# V1.net
KiCad netlist of a schematic drawn in EAGLE
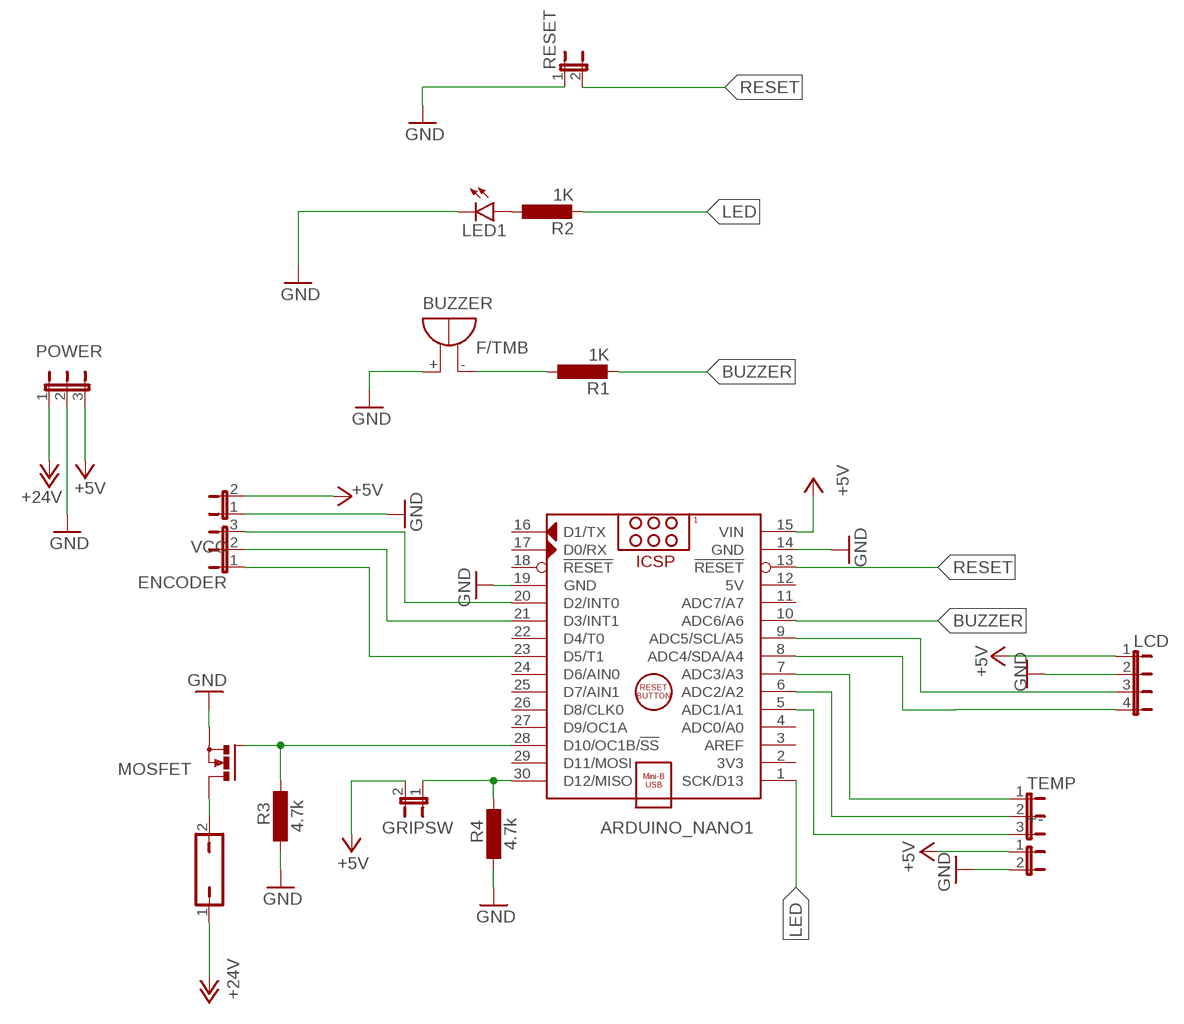
[diagram p0: schematic, sheet 1]

(export (version "E")
  (design (tool "Eeschema 10.0.6"))
  (components
    (comp (ref "+-")
      (value "JP1E")
      (footprint "eagle-import:JP1")
      (libsource (lib "eagle-import") (part "JP1E"))
    )
    (comp (ref "ARDUINO_NANO1")
      (value "ARDUINO_NANO")
      (footprint "eagle-import:ARDUINO_NANO")
      (libsource (lib "eagle-import") (part "ARDUINO_NANO"))
    )
    (comp (ref "BUZZER")
      (value "F/TMB")
      (footprint "eagle-import:F_TMB")
      (libsource (lib "eagle-import") (part "F/TMB"))
    )
    (comp (ref "ENCODER")
      (value "JP2E")
      (footprint "eagle-import:JP2")
      (libsource (lib "eagle-import") (part "JP2E"))
    )
    (comp (ref "GRIPSW")
      (value "JP1E")
      (footprint "eagle-import:JP1")
      (libsource (lib "eagle-import") (part "JP1E"))
    )
    (comp (ref "HEATER")
      (value "794681-2")
      (footprint "eagle-import:JP1")
      (libsource (lib "eagle-import") (part "JP1Q"))
    )
    (comp (ref "LCD")
      (value "JP4E")
      (footprint "eagle-import:JP4")
      (libsource (lib "eagle-import") (part "JP4E"))
    )
    (comp (ref "LED1")
      (value "LED3MM")
      (footprint "eagle-import:LED3MM")
      (libsource (lib "eagle-import") (part "LED3MM"))
    )
    (comp (ref "MOSFET")
      (value "IRLB8721")
      (footprint "eagle-import:TO220BV")
      (libsource (lib "eagle-import") (part "PMOSFET_NTO220BV"))
    )
    (comp (ref "POWER")
      (value "JP2E")
      (footprint "eagle-import:JP2")
      (libsource (lib "eagle-import") (part "JP2E"))
    )
    (comp (ref "R1")
      (value "1K")
      (footprint "eagle-import:0204_7")
      (libsource (lib "eagle-import") (part "L-EU0204/7"))
    )
    (comp (ref "R2")
      (value "1K")
      (footprint "eagle-import:0204_7")
      (libsource (lib "eagle-import") (part "L-EU0204/7"))
    )
    (comp (ref "R3")
      (value "4.7k")
      (footprint "eagle-import:0204_7")
      (libsource (lib "eagle-import") (part "L-EU0204/7"))
    )
    (comp (ref "R4")
      (value "4.7k")
      (footprint "eagle-import:0204_7")
      (libsource (lib "eagle-import") (part "L-EU0204/7"))
    )
    (comp (ref "RESET")
      (value "JP1E")
      (footprint "eagle-import:JP1")
      (libsource (lib "eagle-import") (part "JP1E"))
    )
    (comp (ref "TEMP")
      (value "JP2E")
      (footprint "eagle-import:JP2")
      (libsource (lib "eagle-import") (part "JP2E"))
    )
    (comp (ref "VCC")
      (value "JP1E")
      (footprint "eagle-import:JP1")
      (libsource (lib "eagle-import") (part "JP1E"))
    )
  )
  (nets
    (net (code "1") (name "+5V") (class "Default")
      (node (ref "+-") (pin "1") (pinfunction "1_1") (pintype "passive"))
      (node (ref "ARDUINO_NANO1") (pin "15") (pinfunction "VIN_15") (pintype "power_in"))
      (node (ref "GRIPSW") (pin "2") (pinfunction "2_2") (pintype "passive"))
      (node (ref "LCD") (pin "1") (pinfunction "1_1") (pintype "passive"))
      (node (ref "POWER") (pin "3") (pinfunction "3_3") (pintype "passive"))
      (node (ref "VCC") (pin "2") (pinfunction "2_2") (pintype "passive"))
    )
    (net (code "2") (name "+24V") (class "Default")
      (node (ref "HEATER") (pin "1") (pinfunction "1_1") (pintype "passive"))
      (node (ref "POWER") (pin "1") (pinfunction "1_1") (pintype "passive"))
    )
    (net (code "3") (name "/5V") (class "Default")
      (node (ref "ARDUINO_NANO1") (pin "12") (pinfunction "5V_12") (pintype "power_in"))
    )
    (net (code "4") (name "BUZZER") (class "Default")
      (node (ref "ARDUINO_NANO1") (pin "10") (pinfunction "ADC6/A6_10") (pintype "bidirectional"))
      (node (ref "R1") (pin "2") (pinfunction "2_2") (pintype "passive"))
    )
    (net (code "5") (name "GND") (class "Default")
      (node (ref "+-") (pin "2") (pinfunction "2_2") (pintype "passive"))
      (node (ref "ARDUINO_NANO1") (pin "14") (pinfunction "GND_14") (pintype "power_in"))
      (node (ref "ARDUINO_NANO1") (pin "19") (pinfunction "GND_19") (pintype "power_in"))
      (node (ref "BUZZER") (pin "+") (pinfunction "+_+") (pintype "passive"))
      (node (ref "LCD") (pin "2") (pinfunction "2_2") (pintype "passive"))
      (node (ref "LED1") (pin "K") (pinfunction "C_K") (pintype "passive"))
      (node (ref "MOSFET") (pin "S") (pinfunction "S_S") (pintype "passive"))
      (node (ref "POWER") (pin "2") (pinfunction "2_2") (pintype "passive"))
      (node (ref "R3") (pin "2") (pinfunction "2_2") (pintype "passive"))
      (node (ref "R4") (pin "2") (pinfunction "2_2") (pintype "passive"))
      (node (ref "RESET") (pin "1") (pinfunction "1_1") (pintype "passive"))
      (node (ref "VCC") (pin "1") (pinfunction "1_1") (pintype "passive"))
    )
    (net (code "6") (name "LED") (class "Default")
      (node (ref "ARDUINO_NANO1") (pin "1") (pinfunction "SCK/D13_1") (pintype "bidirectional"))
      (node (ref "R2") (pin "2") (pinfunction "2_2") (pintype "passive"))
    )
    (net (code "7") (name "Net-(ARDUINO_NANO1-ADC1{slash}A1)") (class "Default")
      (node (ref "ARDUINO_NANO1") (pin "5") (pinfunction "ADC1/A1_5") (pintype "bidirectional"))
      (node (ref "TEMP") (pin "3") (pinfunction "3_3") (pintype "passive"))
    )
    (net (code "8") (name "Net-(ARDUINO_NANO1-ADC2{slash}A2)") (class "Default")
      (node (ref "ARDUINO_NANO1") (pin "6") (pinfunction "ADC2/A2_6") (pintype "bidirectional"))
      (node (ref "TEMP") (pin "2") (pinfunction "2_2") (pintype "passive"))
    )
    (net (code "9") (name "Net-(ARDUINO_NANO1-ADC3{slash}A3)") (class "Default")
      (node (ref "ARDUINO_NANO1") (pin "7") (pinfunction "ADC3/A3_7") (pintype "bidirectional"))
      (node (ref "TEMP") (pin "1") (pinfunction "1_1") (pintype "passive"))
    )
    (net (code "10") (name "Net-(ARDUINO_NANO1-ADC4{slash}SDA{slash}A4)") (class "Default")
      (node (ref "ARDUINO_NANO1") (pin "8") (pinfunction "ADC4/SDA/A4_8") (pintype "bidirectional"))
      (node (ref "LCD") (pin "4") (pinfunction "4_4") (pintype "passive"))
    )
    (net (code "11") (name "Net-(ARDUINO_NANO1-ADC5{slash}SCL{slash}A5)") (class "Default")
      (node (ref "ARDUINO_NANO1") (pin "9") (pinfunction "ADC5/SCL/A5_9") (pintype "bidirectional"))
      (node (ref "LCD") (pin "3") (pinfunction "3_3") (pintype "passive"))
    )
    (net (code "12") (name "Net-(ARDUINO_NANO1-D2{slash}INT0)") (class "Default")
      (node (ref "ARDUINO_NANO1") (pin "20") (pinfunction "D2/INT0_20") (pintype "bidirectional"))
      (node (ref "ENCODER") (pin "3") (pinfunction "3_3") (pintype "passive"))
    )
    (net (code "13") (name "Net-(ARDUINO_NANO1-D3{slash}INT1)") (class "Default")
      (node (ref "ARDUINO_NANO1") (pin "21") (pinfunction "D3/INT1_21") (pintype "bidirectional"))
      (node (ref "ENCODER") (pin "2") (pinfunction "2_2") (pintype "passive"))
    )
    (net (code "14") (name "Net-(ARDUINO_NANO1-D5{slash}T1)") (class "Default")
      (node (ref "ARDUINO_NANO1") (pin "23") (pinfunction "D5/T1_23") (pintype "bidirectional"))
      (node (ref "ENCODER") (pin "1") (pinfunction "1_1") (pintype "passive"))
    )
    (net (code "15") (name "Net-(ARDUINO_NANO1-D10{slash}OC1B{slash}~{SS})") (class "Default")
      (node (ref "ARDUINO_NANO1") (pin "28") (pinfunction "D10/OC1B/~{SS}_28") (pintype "bidirectional"))
      (node (ref "MOSFET") (pin "G") (pinfunction "G_G") (pintype "passive"))
      (node (ref "R3") (pin "1") (pinfunction "1_1") (pintype "passive"))
    )
    (net (code "16") (name "Net-(ARDUINO_NANO1-D12{slash}MISO)") (class "Default")
      (node (ref "ARDUINO_NANO1") (pin "30") (pinfunction "D12/MISO_30") (pintype "bidirectional"))
      (node (ref "GRIPSW") (pin "1") (pinfunction "1_1") (pintype "passive"))
      (node (ref "R4") (pin "1") (pinfunction "1_1") (pintype "passive"))
    )
    (net (code "17") (name "Net-(BUZZER-Pad-)") (class "Default")
      (node (ref "BUZZER") (pin "-") (pinfunction "-_-") (pintype "passive"))
      (node (ref "R1") (pin "1") (pinfunction "1_1") (pintype "passive"))
    )
    (net (code "18") (name "Net-(HEATER-Pad2)") (class "Default")
      (node (ref "HEATER") (pin "2") (pinfunction "2_2") (pintype "passive"))
      (node (ref "MOSFET") (pin "D") (pinfunction "D_D") (pintype "passive"))
    )
    (net (code "19") (name "Net-(LED1-PadA)") (class "Default")
      (node (ref "LED1") (pin "A") (pinfunction "A_A") (pintype "passive"))
      (node (ref "R2") (pin "1") (pinfunction "1_1") (pintype "passive"))
    )
    (net (code "20") (name "RESET") (class "Default")
      (node (ref "ARDUINO_NANO1") (pin "13") (pinfunction "~{RESET}_13") (pintype "input"))
      (node (ref "RESET") (pin "2") (pinfunction "2_2") (pintype "passive"))
    )
    (net (code "21") (name "unconnected-(ARDUINO_NANO1-3V3-Pad2)") (class "Default")
      (node (ref "ARDUINO_NANO1") (pin "2") (pinfunction "3V3_2") (pintype "output"))
    )
    (net (code "22") (name "unconnected-(ARDUINO_NANO1-ADC0{slash}A0-Pad4)") (class "Default")
      (node (ref "ARDUINO_NANO1") (pin "4") (pinfunction "ADC0/A0_4") (pintype "bidirectional"))
    )
    (net (code "23") (name "unconnected-(ARDUINO_NANO1-ADC7{slash}A7-Pad11)") (class "Default")
      (node (ref "ARDUINO_NANO1") (pin "11") (pinfunction "ADC7/A7_11") (pintype "bidirectional"))
    )
    (net (code "24") (name "unconnected-(ARDUINO_NANO1-AREF-Pad3)") (class "Default")
      (node (ref "ARDUINO_NANO1") (pin "3") (pinfunction "AREF_3") (pintype "input"))
    )
    (net (code "25") (name "unconnected-(ARDUINO_NANO1-D0{slash}RX-Pad17)") (class "Default")
      (node (ref "ARDUINO_NANO1") (pin "17") (pinfunction "D0/RX_17") (pintype "bidirectional"))
    )
    (net (code "26") (name "unconnected-(ARDUINO_NANO1-D1{slash}TX-Pad16)") (class "Default")
      (node (ref "ARDUINO_NANO1") (pin "16") (pinfunction "D1/TX_16") (pintype "bidirectional"))
    )
    (net (code "27") (name "unconnected-(ARDUINO_NANO1-D4{slash}T0-Pad22)") (class "Default")
      (node (ref "ARDUINO_NANO1") (pin "22") (pinfunction "D4/T0_22") (pintype "bidirectional"))
    )
    (net (code "28") (name "unconnected-(ARDUINO_NANO1-D6{slash}AIN0-Pad24)") (class "Default")
      (node (ref "ARDUINO_NANO1") (pin "24") (pinfunction "D6/AIN0_24") (pintype "bidirectional"))
    )
    (net (code "29") (name "unconnected-(ARDUINO_NANO1-D7{slash}AIN1-Pad25)") (class "Default")
      (node (ref "ARDUINO_NANO1") (pin "25") (pinfunction "D7/AIN1_25") (pintype "bidirectional"))
    )
    (net (code "30") (name "unconnected-(ARDUINO_NANO1-D8{slash}CLK0-Pad26)") (class "Default")
      (node (ref "ARDUINO_NANO1") (pin "26") (pinfunction "D8/CLK0_26") (pintype "bidirectional"))
    )
    (net (code "31") (name "unconnected-(ARDUINO_NANO1-D9{slash}OC1A-Pad27)") (class "Default")
      (node (ref "ARDUINO_NANO1") (pin "27") (pinfunction "D9/OC1A_27") (pintype "bidirectional"))
    )
    (net (code "32") (name "unconnected-(ARDUINO_NANO1-D11{slash}MOSI-Pad29)") (class "Default")
      (node (ref "ARDUINO_NANO1") (pin "29") (pinfunction "D11/MOSI_29") (pintype "bidirectional"))
    )
    (net (code "33") (name "unconnected-(ARDUINO_NANO1-~{RESET}-Pad18)") (class "Default")
      (node (ref "ARDUINO_NANO1") (pin "18") (pinfunction "~{RESET}_18") (pintype "input"))
    )
  )
)
